# AIM2_-_ADCS_REVB.net
KiCad netlist of a schematic drawn in Altium Designer
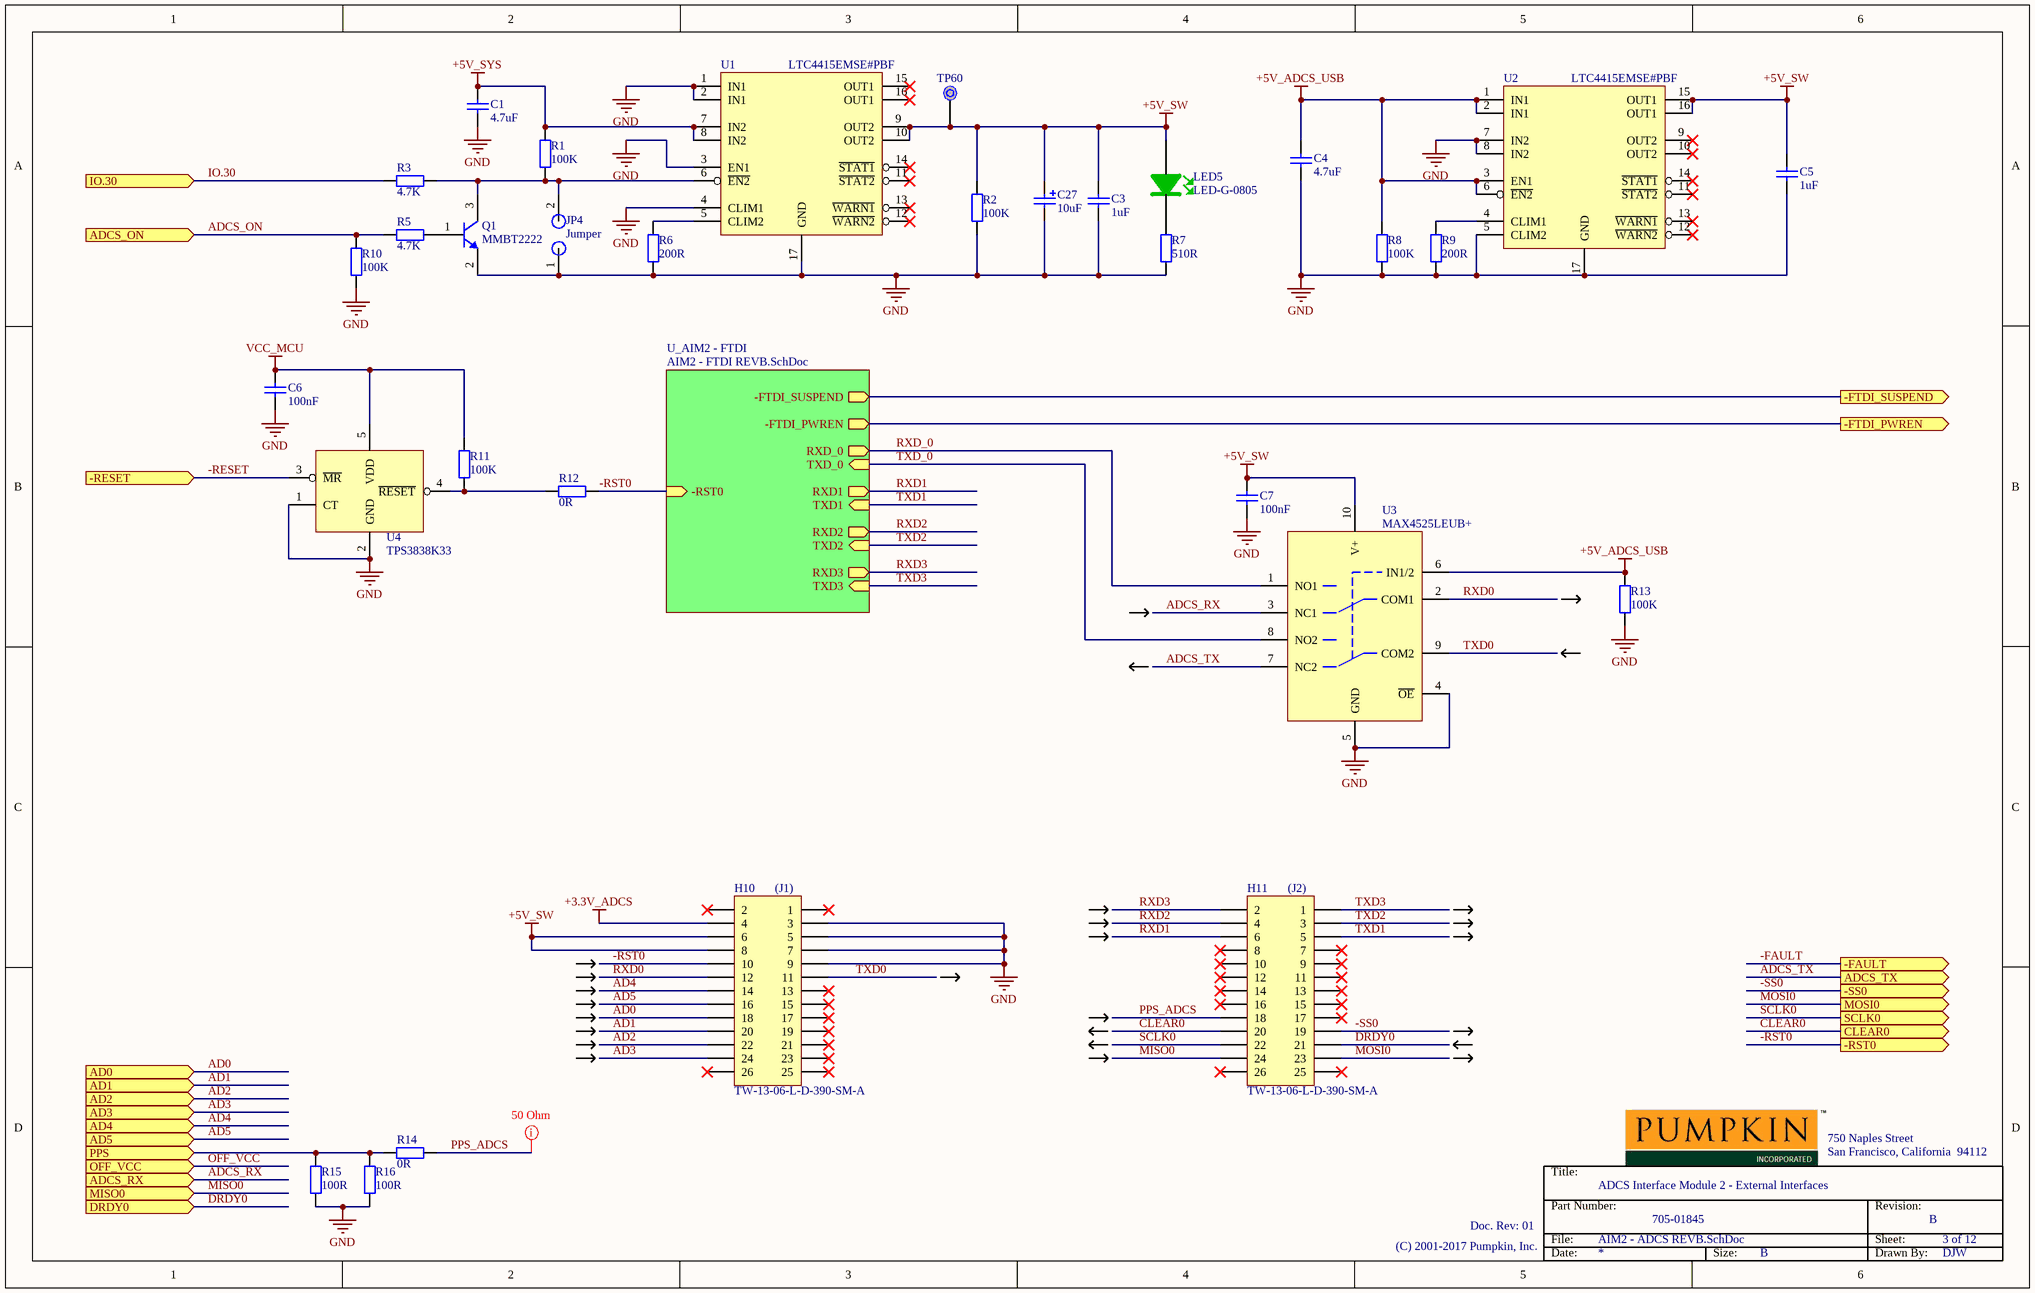
[diagram p0: AIM2 - ADCS REVB.SchDoc]

(export (version "E")
  (design (tool "Eeschema 10.0.6"))
  (components
    (comp (ref "C1")
      (value "4.7uF")
      (footprint "0805 CAP")
      (description "Capacitor 4.7uF 0805 X7R 35V 10%")
      (libsource (lib "Supernova passives") (part "Capacitor 4.7uF 0805"))
    )
    (comp (ref "C3")
      (value "1uF")
      (footprint "0805 CAP")
      (description "Capacitor 1uF 0805 X7R 25V 10%")
      (libsource (lib "Supernova passives") (part "Capacitor 1uF 0805"))
    )
    (comp (ref "C4")
      (value "4.7uF")
      (footprint "0805 CAP")
      (description "Capacitor 4.7uF 0805 X7R 35V 10%")
      (libsource (lib "Supernova passives") (part "Capacitor 4.7uF 0805"))
    )
    (comp (ref "C5")
      (value "1uF")
      (footprint "0805 CAP")
      (description "Capacitor 1uF 0805 X7R 25V 10%")
      (libsource (lib "Supernova passives") (part "Capacitor 1uF 0805"))
    )
    (comp (ref "C6")
      (value "100nF")
      (footprint "0603 CAP")
      (description "Capacitor 100nF 0603 X7R 50V 5%")
      (libsource (lib "Supernova passives") (part "Capacitor 100nF 0603"))
    )
    (comp (ref "C7")
      (value "100nF")
      (footprint "0603 CAP")
      (description "Capacitor 100nF 0603 X7R 50V 5%")
      (libsource (lib "Supernova passives") (part "Capacitor 100nF 0603"))
    )
    (comp (ref "C27")
      (value "10uF")
      (footprint "6032 POLAR CAP")
      (description "Capacitor 10uF 6032 TANT 16V 10%")
      (libsource (lib "Supernova passives") (part "Capacitor 10uF 6032 Tantalum"))
    )
    (comp (ref "H10")
      (value "TW-13-06-L-D-390-SM-A")
      (footprint "TW-13-06-X-D-390-SM-A")
      (description "Header 13x2 TH 2mm pitch")
      (libsource (lib "Supernova") (part "TW-13-06-L-D-390-SM-A"))
    )
    (comp (ref "H11")
      (value "TW-13-06-L-D-390-SM-A")
      (footprint "TW-13-06-X-D-390-SM-A")
      (description "Header 13x2 TH 2mm pitch")
      (libsource (lib "Supernova") (part "TW-13-06-L-D-390-SM-A"))
    )
    (comp (ref "JP4")
      (value "Jumper")
      (footprint "0805 RES 1 way jumper")
      (description "Jumper 0805 1 pos")
      (libsource (lib "Supernova passives") (part "Jumper 1 way 0805"))
    )
    (comp (ref "LED5")
      (value "LED-G-0805")
      (footprint "0805 LED-GREEN")
      (description "LED Green 0805")
      (libsource (lib "Supernova passives") (part "LED GREEN 0805"))
    )
    (comp (ref "Q1")
      (value "MMBT2222")
      (footprint "SOT23-3")
      (description "Transistor NPN")
      (libsource (lib "Supernova") (part "MMBT2222ALT1GOSCT-ND"))
    )
    (comp (ref "R1")
      (value "100K")
      (footprint "0805 RES")
      (description "Resistor 100K 0805 0.5W 1%")
      (libsource (lib "Supernova passives") (part "Resistor 100K 0805"))
    )
    (comp (ref "R2")
      (value "100K")
      (footprint "0805 RES")
      (description "Resistor 100K 0805 0.5W 1%")
      (libsource (lib "Supernova passives") (part "Resistor 100K 0805"))
    )
    (comp (ref "R3")
      (value "4.7K")
      (footprint "0805 RES")
      (description "Resistor 4.7K 0805 0.125W 1%")
      (libsource (lib "Supernova passives") (part "Resistor 4K7 0805"))
    )
    (comp (ref "R5")
      (value "4.7K")
      (footprint "0805 RES")
      (description "Resistor 4.7K 0805 0.125W 1%")
      (libsource (lib "Supernova passives") (part "Resistor 4K7 0805"))
    )
    (comp (ref "R6")
      (value "200R")
      (footprint "0805 RES")
      (description "Resistor 200R 0805 0.125W 1%")
      (libsource (lib "Supernova passives") (part "Resistor 200R 0805"))
    )
    (comp (ref "R7")
      (value "510R")
      (footprint "0805 RES")
      (description "Resistor 470K 0805 0.125W 1%")
      (libsource (lib "Supernova passives") (part "Resistor 510R 0805"))
    )
    (comp (ref "R8")
      (value "100K")
      (footprint "0805 RES")
      (description "Resistor 100K 0805 0.5W 1%")
      (libsource (lib "Supernova passives") (part "Resistor 100K 0805"))
    )
    (comp (ref "R9")
      (value "200R")
      (footprint "0805 RES")
      (description "Resistor 200R 0805 0.125W 1%")
      (libsource (lib "Supernova passives") (part "Resistor 200R 0805"))
    )
    (comp (ref "R10")
      (value "100K")
      (footprint "0805 RES")
      (description "Resistor 100K 0805 0.5W 1%")
      (libsource (lib "Supernova passives") (part "Resistor 100K 0805"))
    )
    (comp (ref "R11")
      (value "100K")
      (footprint "0805 RES")
      (description "Resistor 100K 0805 0.5W 1%")
      (libsource (lib "Supernova passives") (part "Resistor 100K 0805"))
    )
    (comp (ref "R12")
      (value "0R")
      (footprint "0805 RES")
      (description "Resistor 0R 0805 0.125W")
      (libsource (lib "Supernova passives") (part "Resistor 0R 0805"))
    )
    (comp (ref "R13")
      (value "100K")
      (footprint "0805 RES")
      (description "Resistor 100K 0805 0.5W 1%")
      (libsource (lib "Supernova passives") (part "Resistor 100K 0805"))
    )
    (comp (ref "R14")
      (value "0R")
      (footprint "0805 RES")
      (description "Resistor 0R 0805 0.125W")
      (libsource (lib "Supernova passives") (part "Resistor 0R 0805"))
    )
    (comp (ref "R15")
      (value "100R")
      (footprint "0805 RES")
      (description "Resistor 100R 0805 0.125W 1%")
      (libsource (lib "Supernova passives") (part "Resistor 100R 0805"))
    )
    (comp (ref "R16")
      (value "100R")
      (footprint "0805 RES")
      (description "Resistor 100R 0805 0.125W 1%")
      (libsource (lib "Supernova passives") (part "Resistor 100R 0805"))
    )
    (comp (ref "TP60")
      (value "Testpoint")
      (footprint "Testpoint")
      (libsource (lib "Supernova") (part "Testpoint"))
    )
    (comp (ref "U1")
      (value "LTC4415EMSE#PBF")
      (footprint "MSOP-16")
      (description "IC Driver Dual Idewal Diode")
      (libsource (lib "Supernova") (part "LTC4415"))
    )
    (comp (ref "U2")
      (value "LTC4415EMSE#PBF")
      (footprint "MSOP-16")
      (description "IC Driver Dual Idewal Diode")
      (libsource (lib "Supernova") (part "LTC4415"))
    )
    (comp (ref "U3")
      (value "MAX4525LEUB+")
      (footprint "MSOP-10")
      (description "IC Analog Switch DPDT")
      (libsource (lib "Supernova") (part "MAX4525LEUB+"))
    )
    (comp (ref "U4")
      (value "TPS3838K33")
      (footprint "SOT23-5")
      (description "IC Supervisor Reset")
      (libsource (lib "Supernova") (part "TPS3838K33DBVR"))
    )
  )
  (nets
    (net (code "1") (name "+3.3V_ADCS") (class "Default")
      (node (ref "H10") (pin "4") (pinfunction "4_4") (pintype "passive"))
    )
    (net (code "2") (name "+5V_ADCS_USB") (class "Default")
      (node (ref "C4") (pin "2") (pinfunction "2_2") (pintype "passive"))
      (node (ref "R13") (pin "2") (pinfunction "2_2") (pintype "passive"))
      (node (ref "R8") (pin "2") (pinfunction "2_2") (pintype "passive"))
      (node (ref "U2") (pin "1") (pinfunction "IN1_1") (pintype "passive"))
      (node (ref "U2") (pin "2") (pinfunction "IN1_2") (pintype "passive"))
      (node (ref "U2") (pin "3") (pinfunction "EN1_3") (pintype "passive"))
      (node (ref "U2") (pin "6") (pinfunction "~{EN2}_6") (pintype "passive"))
      (node (ref "U3") (pin "6") (pinfunction "IN1/2_6") (pintype "passive"))
    )
    (net (code "3") (name "+5V_SW") (class "Default")
      (node (ref "C27") (pin "1") (pinfunction "1_1") (pintype "passive"))
      (node (ref "C3") (pin "2") (pinfunction "2_2") (pintype "passive"))
      (node (ref "C5") (pin "2") (pinfunction "2_2") (pintype "passive"))
      (node (ref "C7") (pin "2") (pinfunction "2_2") (pintype "passive"))
      (node (ref "H10") (pin "6") (pinfunction "6_6") (pintype "passive"))
      (node (ref "H10") (pin "8") (pinfunction "8_8") (pintype "passive"))
      (node (ref "LED5") (pin "2") (pinfunction "2_2") (pintype "passive"))
      (node (ref "R2") (pin "2") (pinfunction "2_2") (pintype "passive"))
      (node (ref "TP60") (pin "1") (pinfunction "1_1") (pintype "passive"))
      (node (ref "U1") (pin "10") (pinfunction "OUT2_10") (pintype "passive"))
      (node (ref "U1") (pin "9") (pinfunction "OUT2_9") (pintype "passive"))
      (node (ref "U2") (pin "15") (pinfunction "OUT1_15") (pintype "passive"))
      (node (ref "U2") (pin "16") (pinfunction "OUT1_16") (pintype "passive"))
      (node (ref "U3") (pin "10") (pinfunction "V+_10") (pintype "passive"))
    )
    (net (code "4") (name "+5V_SYS") (class "Default")
      (node (ref "C1") (pin "2") (pinfunction "2_2") (pintype "passive"))
      (node (ref "R1") (pin "2") (pinfunction "2_2") (pintype "passive"))
      (node (ref "U1") (pin "7") (pinfunction "IN2_7") (pintype "passive"))
      (node (ref "U1") (pin "8") (pinfunction "IN2_8") (pintype "passive"))
    )
    (net (code "8") (name "/-RESET") (class "Default")
      (node (ref "U4") (pin "3") (pinfunction "~{MR}_3") (pintype "passive"))
    )
    (net (code "9") (name "/-RST0") (class "Default")
      (node (ref "H10") (pin "10") (pinfunction "10_10") (pintype "passive"))
      (node (ref "R12") (pin "2") (pinfunction "2_2") (pintype "passive"))
    )
    (net (code "10") (name "/-SS0") (class "Default")
      (node (ref "H11") (pin "19") (pinfunction "19_19") (pintype "passive"))
    )
    (net (code "11") (name "/AD0") (class "Default")
      (node (ref "H10") (pin "18") (pinfunction "18_18") (pintype "passive"))
    )
    (net (code "12") (name "/AD1") (class "Default")
      (node (ref "H10") (pin "20") (pinfunction "20_20") (pintype "passive"))
    )
    (net (code "13") (name "/AD2") (class "Default")
      (node (ref "H10") (pin "22") (pinfunction "22_22") (pintype "passive"))
    )
    (net (code "14") (name "/AD3") (class "Default")
      (node (ref "H10") (pin "24") (pinfunction "24_24") (pintype "passive"))
    )
    (net (code "15") (name "/AD4") (class "Default")
      (node (ref "H10") (pin "14") (pinfunction "14_14") (pintype "passive"))
    )
    (net (code "16") (name "/AD5") (class "Default")
      (node (ref "H10") (pin "16") (pinfunction "16_16") (pintype "passive"))
    )
    (net (code "17") (name "/ADCS_ON") (class "Default")
      (node (ref "R10") (pin "2") (pinfunction "2_2") (pintype "passive"))
      (node (ref "R5") (pin "1") (pinfunction "1_1") (pintype "passive"))
    )
    (net (code "18") (name "/ADCS_RX") (class "Default")
      (node (ref "U3") (pin "3") (pinfunction "NC1_3") (pintype "passive"))
    )
    (net (code "19") (name "/ADCS_TX") (class "Default")
      (node (ref "U3") (pin "7") (pinfunction "NC2_7") (pintype "passive"))
    )
    (net (code "20") (name "/CLEAR0") (class "Default")
      (node (ref "H11") (pin "20") (pinfunction "20_20") (pintype "passive"))
    )
    (net (code "21") (name "/DRDY0") (class "Default")
      (node (ref "H11") (pin "21") (pinfunction "21_21") (pintype "passive"))
    )
    (net (code "22") (name "/IO.30") (class "Default")
      (node (ref "R3") (pin "1") (pinfunction "1_1") (pintype "passive"))
    )
    (net (code "23") (name "/MISO0") (class "Default")
      (node (ref "H11") (pin "24") (pinfunction "24_24") (pintype "passive"))
    )
    (net (code "24") (name "/MOSI0") (class "Default")
      (node (ref "H11") (pin "23") (pinfunction "23_23") (pintype "passive"))
    )
    (net (code "26") (name "/PPS") (class "Default")
      (node (ref "R14") (pin "1") (pinfunction "1_1") (pintype "passive"))
      (node (ref "R15") (pin "2") (pinfunction "2_2") (pintype "passive"))
      (node (ref "R16") (pin "2") (pinfunction "2_2") (pintype "passive"))
    )
    (net (code "27") (name "/PPS_ADCS") (class "Default")
      (node (ref "H11") (pin "18") (pinfunction "18_18") (pintype "passive"))
      (node (ref "R14") (pin "2") (pinfunction "2_2") (pintype "passive"))
    )
    (net (code "28") (name "/RXD0") (class "Default")
      (node (ref "H10") (pin "12") (pinfunction "12_12") (pintype "passive"))
      (node (ref "U3") (pin "2") (pinfunction "COM1_2") (pintype "passive"))
    )
    (net (code "29") (name "/RXD1") (class "Default")
      (node (ref "H11") (pin "6") (pinfunction "6_6") (pintype "passive"))
    )
    (net (code "30") (name "/RXD2") (class "Default")
      (node (ref "H11") (pin "4") (pinfunction "4_4") (pintype "passive"))
    )
    (net (code "31") (name "/RXD3") (class "Default")
      (node (ref "H11") (pin "2") (pinfunction "2_2") (pintype "passive"))
    )
    (net (code "32") (name "/RXD_0") (class "Default")
      (node (ref "U3") (pin "1") (pinfunction "NO1_1") (pintype "passive"))
    )
    (net (code "33") (name "/SCLK0") (class "Default")
      (node (ref "H11") (pin "22") (pinfunction "22_22") (pintype "passive"))
    )
    (net (code "34") (name "/TXD0") (class "Default")
      (node (ref "H10") (pin "11") (pinfunction "11_11") (pintype "passive"))
      (node (ref "U3") (pin "9") (pinfunction "COM2_9") (pintype "passive"))
    )
    (net (code "35") (name "/TXD1") (class "Default")
      (node (ref "H11") (pin "5") (pinfunction "5_5") (pintype "passive"))
    )
    (net (code "36") (name "/TXD2") (class "Default")
      (node (ref "H11") (pin "3") (pinfunction "3_3") (pintype "passive"))
    )
    (net (code "37") (name "/TXD3") (class "Default")
      (node (ref "H11") (pin "1") (pinfunction "1_1") (pintype "passive"))
    )
    (net (code "38") (name "/TXD_0") (class "Default")
      (node (ref "U3") (pin "8") (pinfunction "NO2_8") (pintype "passive"))
    )
    (net (code "39") (name "GND") (class "Default")
      (node (ref "C1") (pin "1") (pinfunction "1_1") (pintype "passive"))
      (node (ref "C27") (pin "2") (pinfunction "2_2") (pintype "passive"))
      (node (ref "C3") (pin "1") (pinfunction "1_1") (pintype "passive"))
      (node (ref "C4") (pin "1") (pinfunction "1_1") (pintype "passive"))
      (node (ref "C5") (pin "1") (pinfunction "1_1") (pintype "passive"))
      (node (ref "C6") (pin "1") (pinfunction "1_1") (pintype "passive"))
      (node (ref "C7") (pin "1") (pinfunction "1_1") (pintype "passive"))
      (node (ref "H10") (pin "3") (pinfunction "3_3") (pintype "passive"))
      (node (ref "H10") (pin "5") (pinfunction "5_5") (pintype "passive"))
      (node (ref "H10") (pin "7") (pinfunction "7_7") (pintype "passive"))
      (node (ref "H10") (pin "9") (pinfunction "9_9") (pintype "passive"))
      (node (ref "JP4") (pin "1") (pinfunction "5_1") (pintype "passive"))
      (node (ref "Q1") (pin "2") (pinfunction "E_2") (pintype "passive"))
      (node (ref "R10") (pin "1") (pinfunction "1_1") (pintype "passive"))
      (node (ref "R13") (pin "1") (pinfunction "1_1") (pintype "passive"))
      (node (ref "R15") (pin "1") (pinfunction "1_1") (pintype "passive"))
      (node (ref "R16") (pin "1") (pinfunction "1_1") (pintype "passive"))
      (node (ref "R2") (pin "1") (pinfunction "1_1") (pintype "passive"))
      (node (ref "R6") (pin "1") (pinfunction "1_1") (pintype "passive"))
      (node (ref "R7") (pin "1") (pinfunction "1_1") (pintype "passive"))
      (node (ref "R8") (pin "1") (pinfunction "1_1") (pintype "passive"))
      (node (ref "R9") (pin "1") (pinfunction "1_1") (pintype "passive"))
      (node (ref "U1") (pin "1") (pinfunction "IN1_1") (pintype "passive"))
      (node (ref "U1") (pin "17") (pinfunction "GND_17") (pintype "passive"))
      (node (ref "U1") (pin "2") (pinfunction "IN1_2") (pintype "passive"))
      (node (ref "U1") (pin "3") (pinfunction "EN1_3") (pintype "passive"))
      (node (ref "U1") (pin "4") (pinfunction "CLIM1_4") (pintype "passive"))
      (node (ref "U2") (pin "17") (pinfunction "GND_17") (pintype "passive"))
      (node (ref "U2") (pin "5") (pinfunction "CLIM2_5") (pintype "passive"))
      (node (ref "U2") (pin "7") (pinfunction "IN2_7") (pintype "passive"))
      (node (ref "U2") (pin "8") (pinfunction "IN2_8") (pintype "passive"))
      (node (ref "U3") (pin "4") (pinfunction "~{OE}_4") (pintype "passive"))
      (node (ref "U3") (pin "5") (pinfunction "GND_5") (pintype "passive"))
      (node (ref "U4") (pin "1") (pinfunction "CT_1") (pintype "passive"))
      (node (ref "U4") (pin "2") (pinfunction "GND_2") (pintype "passive"))
    )
    (net (code "40") (name "Net-(LED5-Pad1)") (class "Default")
      (node (ref "LED5") (pin "1") (pinfunction "1_1") (pintype "passive"))
      (node (ref "R7") (pin "2") (pinfunction "2_2") (pintype "passive"))
    )
    (net (code "41") (name "Net-(Q1-B)") (class "Default")
      (node (ref "Q1") (pin "1") (pinfunction "B_1") (pintype "passive"))
      (node (ref "R5") (pin "2") (pinfunction "2_2") (pintype "passive"))
    )
    (net (code "42") (name "Net-(Q1-C)") (class "Default")
      (node (ref "JP4") (pin "2") (pinfunction "5_2") (pintype "passive"))
      (node (ref "Q1") (pin "3") (pinfunction "C_3") (pintype "passive"))
      (node (ref "R1") (pin "1") (pinfunction "1_1") (pintype "passive"))
      (node (ref "R3") (pin "2") (pinfunction "2_2") (pintype "passive"))
      (node (ref "U1") (pin "6") (pinfunction "~{EN2}_6") (pintype "passive"))
    )
    (net (code "43") (name "Net-(U1-CLIM2)") (class "Default")
      (node (ref "R6") (pin "2") (pinfunction "2_2") (pintype "passive"))
      (node (ref "U1") (pin "5") (pinfunction "CLIM2_5") (pintype "passive"))
    )
    (net (code "44") (name "Net-(U2-CLIM1)") (class "Default")
      (node (ref "R9") (pin "2") (pinfunction "2_2") (pintype "passive"))
      (node (ref "U2") (pin "4") (pinfunction "CLIM1_4") (pintype "passive"))
    )
    (net (code "45") (name "Net-(U4-~{RESET})") (class "Default")
      (node (ref "R11") (pin "1") (pinfunction "1_1") (pintype "passive"))
      (node (ref "R12") (pin "1") (pinfunction "1_1") (pintype "passive"))
      (node (ref "U4") (pin "4") (pinfunction "~{RESET}_4") (pintype "passive"))
    )
    (net (code "46") (name "VCC_MCU") (class "Default")
      (node (ref "C6") (pin "2") (pinfunction "2_2") (pintype "passive"))
      (node (ref "R11") (pin "2") (pinfunction "2_2") (pintype "passive"))
      (node (ref "U4") (pin "5") (pinfunction "VDD_5") (pintype "passive"))
    )
    (net (code "47") (name "unconnected-(H10-Pad1)") (class "Default")
      (node (ref "H10") (pin "1") (pinfunction "1_1") (pintype "passive+no_connect"))
    )
    (net (code "48") (name "unconnected-(H10-Pad2)") (class "Default")
      (node (ref "H10") (pin "2") (pinfunction "2_2") (pintype "passive+no_connect"))
    )
    (net (code "49") (name "unconnected-(H10-Pad13)") (class "Default")
      (node (ref "H10") (pin "13") (pinfunction "13_13") (pintype "passive+no_connect"))
    )
    (net (code "50") (name "unconnected-(H10-Pad15)") (class "Default")
      (node (ref "H10") (pin "15") (pinfunction "15_15") (pintype "passive+no_connect"))
    )
    (net (code "51") (name "unconnected-(H10-Pad17)") (class "Default")
      (node (ref "H10") (pin "17") (pinfunction "17_17") (pintype "passive+no_connect"))
    )
    (net (code "52") (name "unconnected-(H10-Pad19)") (class "Default")
      (node (ref "H10") (pin "19") (pinfunction "19_19") (pintype "passive+no_connect"))
    )
    (net (code "53") (name "unconnected-(H10-Pad21)") (class "Default")
      (node (ref "H10") (pin "21") (pinfunction "21_21") (pintype "passive+no_connect"))
    )
    (net (code "54") (name "unconnected-(H10-Pad23)") (class "Default")
      (node (ref "H10") (pin "23") (pinfunction "23_23") (pintype "passive+no_connect"))
    )
    (net (code "55") (name "unconnected-(H10-Pad25)") (class "Default")
      (node (ref "H10") (pin "25") (pinfunction "25_25") (pintype "passive+no_connect"))
    )
    (net (code "56") (name "unconnected-(H10-Pad26)") (class "Default")
      (node (ref "H10") (pin "26") (pinfunction "26_26") (pintype "passive+no_connect"))
    )
    (net (code "57") (name "unconnected-(H11-Pad7)") (class "Default")
      (node (ref "H11") (pin "7") (pinfunction "7_7") (pintype "passive+no_connect"))
    )
    (net (code "58") (name "unconnected-(H11-Pad8)") (class "Default")
      (node (ref "H11") (pin "8") (pinfunction "8_8") (pintype "passive+no_connect"))
    )
    (net (code "59") (name "unconnected-(H11-Pad9)") (class "Default")
      (node (ref "H11") (pin "9") (pinfunction "9_9") (pintype "passive+no_connect"))
    )
    (net (code "60") (name "unconnected-(H11-Pad10)") (class "Default")
      (node (ref "H11") (pin "10") (pinfunction "10_10") (pintype "passive+no_connect"))
    )
    (net (code "61") (name "unconnected-(H11-Pad11)") (class "Default")
      (node (ref "H11") (pin "11") (pinfunction "11_11") (pintype "passive+no_connect"))
    )
    (net (code "62") (name "unconnected-(H11-Pad12)") (class "Default")
      (node (ref "H11") (pin "12") (pinfunction "12_12") (pintype "passive+no_connect"))
    )
    (net (code "63") (name "unconnected-(H11-Pad13)") (class "Default")
      (node (ref "H11") (pin "13") (pinfunction "13_13") (pintype "passive+no_connect"))
    )
    (net (code "64") (name "unconnected-(H11-Pad14)") (class "Default")
      (node (ref "H11") (pin "14") (pinfunction "14_14") (pintype "passive+no_connect"))
    )
    (net (code "65") (name "unconnected-(H11-Pad15)") (class "Default")
      (node (ref "H11") (pin "15") (pinfunction "15_15") (pintype "passive+no_connect"))
    )
    (net (code "66") (name "unconnected-(H11-Pad16)") (class "Default")
      (node (ref "H11") (pin "16") (pinfunction "16_16") (pintype "passive+no_connect"))
    )
    (net (code "67") (name "unconnected-(H11-Pad17)") (class "Default")
      (node (ref "H11") (pin "17") (pinfunction "17_17") (pintype "passive+no_connect"))
    )
    (net (code "68") (name "unconnected-(H11-Pad25)") (class "Default")
      (node (ref "H11") (pin "25") (pinfunction "25_25") (pintype "passive+no_connect"))
    )
    (net (code "69") (name "unconnected-(H11-Pad26)") (class "Default")
      (node (ref "H11") (pin "26") (pinfunction "26_26") (pintype "passive+no_connect"))
    )
    (net (code "70") (name "unconnected-(U1-OUT1-Pad15)") (class "Default")
      (node (ref "U1") (pin "15") (pinfunction "OUT1_15") (pintype "passive+no_connect"))
    )
    (net (code "71") (name "unconnected-(U1-OUT1-Pad16)") (class "Default")
      (node (ref "U1") (pin "16") (pinfunction "OUT1_16") (pintype "passive+no_connect"))
    )
    (net (code "72") (name "unconnected-(U1-~{STAT1}-Pad14)") (class "Default")
      (node (ref "U1") (pin "14") (pinfunction "~{STAT1}_14") (pintype "passive+no_connect"))
    )
    (net (code "73") (name "unconnected-(U1-~{STAT2}-Pad11)") (class "Default")
      (node (ref "U1") (pin "11") (pinfunction "~{STAT2}_11") (pintype "passive+no_connect"))
    )
    (net (code "74") (name "unconnected-(U1-~{WARN1}-Pad13)") (class "Default")
      (node (ref "U1") (pin "13") (pinfunction "~{WARN1}_13") (pintype "passive+no_connect"))
    )
    (net (code "75") (name "unconnected-(U1-~{WARN2}-Pad12)") (class "Default")
      (node (ref "U1") (pin "12") (pinfunction "~{WARN2}_12") (pintype "passive+no_connect"))
    )
    (net (code "76") (name "unconnected-(U2-OUT2-Pad9)") (class "Default")
      (node (ref "U2") (pin "9") (pinfunction "OUT2_9") (pintype "passive+no_connect"))
    )
    (net (code "77") (name "unconnected-(U2-OUT2-Pad10)") (class "Default")
      (node (ref "U2") (pin "10") (pinfunction "OUT2_10") (pintype "passive+no_connect"))
    )
    (net (code "78") (name "unconnected-(U2-~{STAT1}-Pad14)") (class "Default")
      (node (ref "U2") (pin "14") (pinfunction "~{STAT1}_14") (pintype "passive+no_connect"))
    )
    (net (code "79") (name "unconnected-(U2-~{STAT2}-Pad11)") (class "Default")
      (node (ref "U2") (pin "11") (pinfunction "~{STAT2}_11") (pintype "passive+no_connect"))
    )
    (net (code "80") (name "unconnected-(U2-~{WARN1}-Pad13)") (class "Default")
      (node (ref "U2") (pin "13") (pinfunction "~{WARN1}_13") (pintype "passive+no_connect"))
    )
    (net (code "81") (name "unconnected-(U2-~{WARN2}-Pad12)") (class "Default")
      (node (ref "U2") (pin "12") (pinfunction "~{WARN2}_12") (pintype "passive+no_connect"))
    )
  )
)
